# Control.net
KiCad netlist of a schematic drawn in Altium Designer
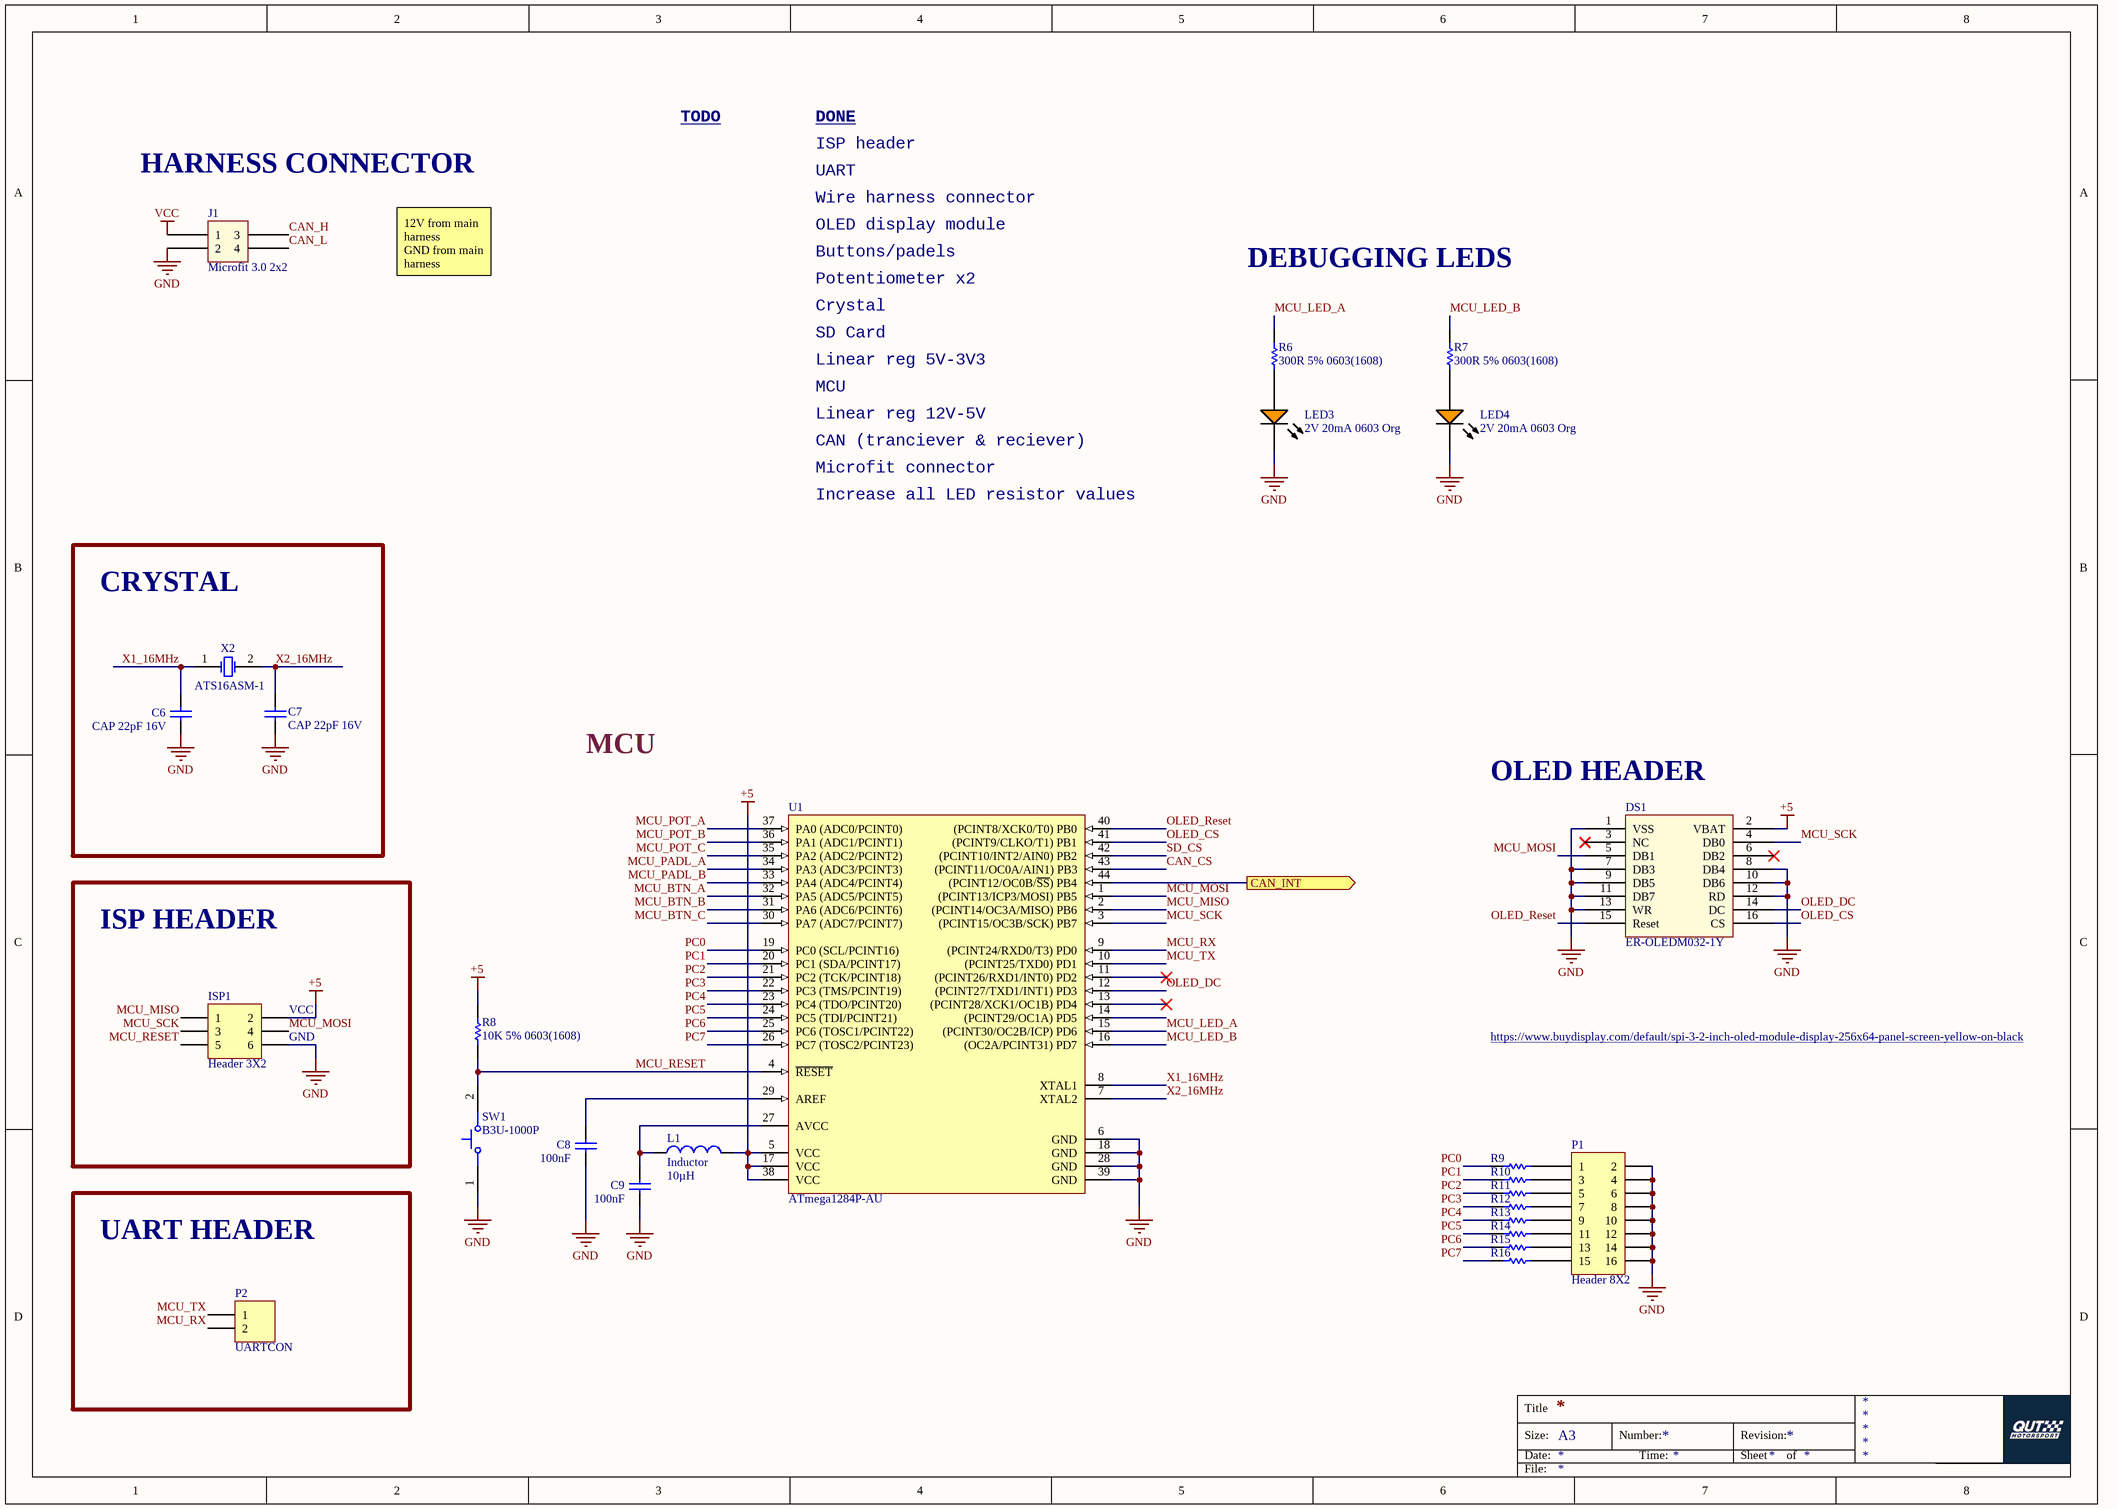
[diagram p0: Control.SchDoc]

(export (version "E")
  (design (tool "Eeschema 10.0.6"))
  (components
    (comp (ref "C6")
      (value "CAP 22pF 16V")
      (footprint "CAPC0603(1608)100_N")
      (description "CAP 22pF 16V ±5% 0603 (1608 Metric) Thickness 1mm SMD")
      (fields (field (name "TOLERANCE") "Â±5%"))
      (libsource (lib "Altium Content Vault") (part "CAP"))
    )
    (comp (ref "C7")
      (value "CAP 22pF 16V")
      (footprint "CAPC0603(1608)100_N")
      (description "CAP 22pF 16V ±5% 0603 (1608 Metric) Thickness 1mm SMD")
      (fields (field (name "TOLERANCE") "Â±5%"))
      (libsource (lib "Altium Content Vault") (part "CAP"))
    )
    (comp (ref "C8")
      (value "100nF")
      (footprint "CAPC0603(1608)100_M")
      (description "CAP 100nF 16V ±5% 0603 (1608 Metric) Thickness 1mm SMD")
      (fields (field (name "TOLERANCE") "Â±5%"))
      (libsource (lib "Altium Content Vault") (part "CAP"))
    )
    (comp (ref "C9")
      (value "100nF")
      (footprint "CAPC0603(1608)100_M")
      (description "CAP 100nF 16V ±5% 0603 (1608 Metric) Thickness 1mm SMD")
      (fields (field (name "TOLERANCE") "Â±5%"))
      (libsource (lib "Altium Content Vault") (part "CAP"))
    )
    (comp (ref "DS1")
      (value "ER-OLEDM032-1Y")
      (footprint "ER-OLEDM032-1Y")
      (description "SPI 3.2 inch OLED Module Display 256x64 Panel Screen,Yellow on Black")
      (libsource (lib "QUTMS_SteeringWheel") (part "ER-OLEDM032-1Y"))
    )
    (comp (ref "ISP1")
      (value "Header 3X2")
      (footprint "HDR2X3")
      (description "Header, 3-Pin, Dual row")
      (fields (field (name "PUBLISHER") "Altium Limited"))
      (libsource (lib "Miscellaneous Connectors") (part "Header 3X2"))
    )
    (comp (ref "J1")
      (value "Microfit 3.0 2x2")
      (footprint "Microfit_2X2_R_TH")
      (libsource (lib "QUTMS_Microfit") (part "Microfit_2x2"))
    )
    (comp (ref "L1")
      (value "Inductor")
      (footprint "0603")
      (fields (field (name "ALTIUM_VALUE") "10µH") (field (name "PUBLISHER") "Altium Limited"))
      (libsource (lib "Miscellaneous Devices") (part "Inductor"))
    )
    (comp (ref "LED3")
      (value "2V 20mA 0603 Org")
      (footprint "KING-LED0603-25-ORANGE_V")
      (description "LED, SMT, 0603(1608), 0.25mm Tthickness, Super Bright Orange")
      (fields (field (name "PARTNUMBER") "APG1608SEKC/T"))
      (libsource (lib "Altium Content Vault") (part "KING-LED_ORANGE_A1K2-2"))
    )
    (comp (ref "LED4")
      (value "2V 20mA 0603 Org")
      (footprint "KING-LED0603-25-ORANGE_V")
      (description "LED, SMT, 0603(1608), 0.25mm Tthickness, Super Bright Orange")
      (fields (field (name "PARTNUMBER") "APG1608SEKC/T"))
      (libsource (lib "Altium Content Vault") (part "KING-LED_ORANGE_A1K2-2"))
    )
    (comp (ref "P1")
      (value "Header 8X2")
      (footprint "HDR2X8")
      (description "Header, 8-Pin, Dual row")
      (fields (field (name "PUBLISHER") "Altium Limited"))
      (libsource (lib "Miscellaneous Connectors") (part "Header 8X2"))
    )
    (comp (ref "P2")
      (value "UARTCON")
      (footprint "HDR1X2")
      (description "Header, 2-Pin")
      (fields (field (name "PUBLISHER") "Altium Limited"))
      (libsource (lib "Miscellaneous Connectors") (part "Header 2"))
    )
    (comp (ref "R6")
      (value "300R 5% 0603(1608)")
      (footprint "RESC0603(1608)_N")
      (description "300R 0.1W 5% 0603 (1608 Metric)  SMD")
      (fields (field (name "TOLERANCE") "5 %") (field (name "POWER") "0.1 W"))
      (libsource (lib "Altium Content Vault") (part "RES"))
    )
    (comp (ref "R7")
      (value "300R 5% 0603(1608)")
      (footprint "RESC0603(1608)_N")
      (description "300R 0.1W 5% 0603 (1608 Metric)  SMD")
      (fields (field (name "TOLERANCE") "5 %") (field (name "POWER") "0.1 W"))
      (libsource (lib "Altium Content Vault") (part "RES"))
    )
    (comp (ref "R8")
      (value "10K 5% 0603(1608)")
      (footprint "RESC0603(1608)_N")
      (description "10K 0.1W 5% 0603 (1608 Metric)  SMD")
      (fields (field (name "TOLERANCE") "5 %") (field (name "POWER") "0.1 W"))
      (libsource (lib "Altium Content Vault") (part "RES"))
    )
    (comp (ref "R9")
      (value "JMP")
      (footprint "RESC0603(1608)_N")
      (description "300R 0.1W 5% 0603 (1608 Metric)  SMD")
      (fields (field (name "TOLERANCE") "5 %") (field (name "POWER") "0.1 W"))
      (libsource (lib "Altium Content Vault") (part "RES"))
    )
    (comp (ref "R10")
      (value "JMP")
      (footprint "RESC0603(1608)_N")
      (description "300R 0.1W 5% 0603 (1608 Metric)  SMD")
      (fields (field (name "TOLERANCE") "5 %") (field (name "POWER") "0.1 W"))
      (libsource (lib "Altium Content Vault") (part "RES"))
    )
    (comp (ref "R11")
      (value "JMP")
      (footprint "RESC0603(1608)_N")
      (description "300R 0.1W 5% 0603 (1608 Metric)  SMD")
      (fields (field (name "TOLERANCE") "5 %") (field (name "POWER") "0.1 W"))
      (libsource (lib "Altium Content Vault") (part "RES"))
    )
    (comp (ref "R12")
      (value "JMP")
      (footprint "RESC0603(1608)_N")
      (description "300R 0.1W 5% 0603 (1608 Metric)  SMD")
      (fields (field (name "TOLERANCE") "5 %") (field (name "POWER") "0.1 W"))
      (libsource (lib "Altium Content Vault") (part "RES"))
    )
    (comp (ref "R13")
      (value "JMP")
      (footprint "RESC0603(1608)_N")
      (description "300R 0.1W 5% 0603 (1608 Metric)  SMD")
      (fields (field (name "TOLERANCE") "5 %") (field (name "POWER") "0.1 W"))
      (libsource (lib "Altium Content Vault") (part "RES"))
    )
    (comp (ref "R14")
      (value "JMP")
      (footprint "RESC0603(1608)_N")
      (description "300R 0.1W 5% 0603 (1608 Metric)  SMD")
      (fields (field (name "TOLERANCE") "5 %") (field (name "POWER") "0.1 W"))
      (libsource (lib "Altium Content Vault") (part "RES"))
    )
    (comp (ref "R15")
      (value "JMP")
      (footprint "RESC0603(1608)_N")
      (description "300R 0.1W 5% 0603 (1608 Metric)  SMD")
      (fields (field (name "TOLERANCE") "5 %") (field (name "POWER") "0.1 W"))
      (libsource (lib "Altium Content Vault") (part "RES"))
    )
    (comp (ref "R16")
      (value "~")
      (footprint "RESC0603(1608)_N")
      (description "300R 0.1W 5% 0603 (1608 Metric)  SMD")
      (fields (field (name "TOLERANCE") "5 %") (field (name "POWER") "0.1 W"))
      (libsource (lib "Altium Content Vault") (part "RES"))
    )
    (comp (ref "SW1")
      (value "B3U-1000P")
      (footprint "OMRON-B3U-1000_V")
      (description "Ultra-Small Tactile Switch, 0.05 A, 12 V, -25 to 70 degC, 2-Pin SMD, RoHS, Tape and Reel")
      (fields (field (name "MANUFACTURER") "Omron Electronic Components"))
      (libsource (lib "Altium Content Vault") (part "SW-SPST-NO-2"))
    )
    (comp (ref "U1")
      (value "ATmega1284P-AU")
      (footprint "44A_N")
      (description "20 MHz 8-bit AVR Microcontroller with 128KB Flash, 44-Pin TQFP Pkg, Industrial Temp")
      (libsource (lib "Altium Content Vault") (part "MC-8B-ATmega1284P-44"))
    )
    (comp (ref "X2")
      (value "ATS16ASM-1")
      (footprint "CTS-ATS-SM-XTAL-2")
      (description "ATS-SM Series Quartz Crystal, 16 MHz, -20 to 70 degC, 11.1 x 4.83 x 4.3mm SMD, RoHS, Tape and Reel")
      (fields (field (name "MANUFACTURER") "CTS Corporation"))
      (libsource (lib "Altium Content Vault") (part "CTS-ATS-SM-XTAL-2"))
    )
  )
  (nets
    (net (code "1") (name "+5") (class "Default")
      (node (ref "DS1") (pin "2") (pinfunction "VBAT_2") (pintype "passive"))
      (node (ref "ISP1") (pin "2") (pinfunction "2_2") (pintype "passive"))
      (node (ref "L1") (pin "2") (pinfunction "2_2") (pintype "passive"))
      (node (ref "R8") (pin "2") (pinfunction "2_2") (pintype "passive"))
      (node (ref "U1") (pin "17") (pinfunction "VCC_17") (pintype "passive"))
      (node (ref "U1") (pin "38") (pinfunction "VCC_38") (pintype "passive"))
      (node (ref "U1") (pin "5") (pinfunction "VCC_5") (pintype "passive"))
    )
    (net (code "2") (name "/CAN_CS") (class "Default")
      (node (ref "U1") (pin "43") (pinfunction "(PCINT11/OC0A/AIN1)_PB3_43") (pintype "input"))
    )
    (net (code "3") (name "/CAN_H") (class "Default")
      (node (ref "J1") (pin "3") (pinfunction "3_3") (pintype "passive"))
    )
    (net (code "4") (name "/CAN_INT") (class "Default")
      (node (ref "U1") (pin "44") (pinfunction "(PCINT12/OC0B/~{SS})_PB4_44") (pintype "input"))
    )
    (net (code "5") (name "/CAN_L") (class "Default")
      (node (ref "J1") (pin "4") (pinfunction "4_4") (pintype "passive"))
    )
    (net (code "6") (name "/MCU_BTN_A") (class "Default")
      (node (ref "U1") (pin "32") (pinfunction "PA5_(ADC5/PCINT5)_32") (pintype "input"))
    )
    (net (code "7") (name "/MCU_BTN_B") (class "Default")
      (node (ref "U1") (pin "31") (pinfunction "PA6_(ADC6/PCINT6)_31") (pintype "input"))
    )
    (net (code "8") (name "/MCU_BTN_C") (class "Default")
      (node (ref "U1") (pin "30") (pinfunction "PA7_(ADC7/PCINT7)_30") (pintype "input"))
    )
    (net (code "9") (name "/MCU_LED_A") (class "Default")
      (node (ref "R6") (pin "2") (pinfunction "2_2") (pintype "passive"))
      (node (ref "U1") (pin "15") (pinfunction "(PCINT30/OC2B/ICP)_PD6_15") (pintype "input"))
    )
    (net (code "10") (name "/MCU_LED_B") (class "Default")
      (node (ref "R7") (pin "2") (pinfunction "2_2") (pintype "passive"))
      (node (ref "U1") (pin "16") (pinfunction "(OC2A/PCINT31)_PD7_16") (pintype "input"))
    )
    (net (code "11") (name "/MCU_MISO") (class "Default")
      (node (ref "ISP1") (pin "1") (pinfunction "1_1") (pintype "passive"))
      (node (ref "U1") (pin "2") (pinfunction "(PCINT14/OC3A/MISO)_PB6_2") (pintype "input"))
    )
    (net (code "12") (name "/MCU_MOSI") (class "Default")
      (node (ref "DS1") (pin "5") (pinfunction "DB1_5") (pintype "passive"))
      (node (ref "ISP1") (pin "4") (pinfunction "4_4") (pintype "passive"))
      (node (ref "U1") (pin "1") (pinfunction "(PCINT13/ICP3/MOSI)_PB5_1") (pintype "input"))
    )
    (net (code "13") (name "/MCU_PADL_A") (class "Default")
      (node (ref "U1") (pin "34") (pinfunction "PA3_(ADC3/PCINT3)_34") (pintype "input"))
    )
    (net (code "14") (name "/MCU_PADL_B") (class "Default")
      (node (ref "U1") (pin "33") (pinfunction "PA4_(ADC4/PCINT4)_33") (pintype "input"))
    )
    (net (code "15") (name "/MCU_POT_A") (class "Default")
      (node (ref "U1") (pin "37") (pinfunction "PA0_(ADC0/PCINT0)_37") (pintype "input"))
    )
    (net (code "16") (name "/MCU_POT_B") (class "Default")
      (node (ref "U1") (pin "36") (pinfunction "PA1_(ADC1/PCINT1)_36") (pintype "input"))
    )
    (net (code "17") (name "/MCU_POT_C") (class "Default")
      (node (ref "U1") (pin "35") (pinfunction "PA2_(ADC2/PCINT2)_35") (pintype "input"))
    )
    (net (code "18") (name "/MCU_RESET") (class "Default")
      (node (ref "ISP1") (pin "5") (pinfunction "5_5") (pintype "passive"))
      (node (ref "R8") (pin "1") (pinfunction "1_1") (pintype "passive"))
      (node (ref "SW1") (pin "2") (pinfunction "2_2") (pintype "passive"))
      (node (ref "U1") (pin "4") (pinfunction "~{RESET}_4") (pintype "input"))
    )
    (net (code "19") (name "/MCU_RX") (class "Default")
      (node (ref "P2") (pin "2") (pinfunction "2_2") (pintype "passive"))
      (node (ref "U1") (pin "9") (pinfunction "(PCINT24/RXD0/T3)_PD0_9") (pintype "input"))
    )
    (net (code "20") (name "/MCU_SCK") (class "Default")
      (node (ref "DS1") (pin "4") (pinfunction "DB0_4") (pintype "passive"))
      (node (ref "ISP1") (pin "3") (pinfunction "3_3") (pintype "passive"))
      (node (ref "U1") (pin "3") (pinfunction "(PCINT15/OC3B/SCK)_PB7_3") (pintype "input"))
    )
    (net (code "21") (name "/MCU_TX") (class "Default")
      (node (ref "P2") (pin "1") (pinfunction "1_1") (pintype "passive"))
      (node (ref "U1") (pin "10") (pinfunction "(PCINT25/TXD0)_PD1_10") (pintype "input"))
    )
    (net (code "22") (name "/OLED_CS") (class "Default")
      (node (ref "DS1") (pin "16") (pinfunction "CS_16") (pintype "passive"))
      (node (ref "U1") (pin "41") (pinfunction "(PCINT9/CLKO/T1)_PB1_41") (pintype "input"))
    )
    (net (code "23") (name "/OLED_DC") (class "Default")
      (node (ref "DS1") (pin "14") (pinfunction "DC_14") (pintype "passive"))
      (node (ref "U1") (pin "12") (pinfunction "(PCINT27/TXD1/INT1)_PD3_12") (pintype "input"))
    )
    (net (code "24") (name "/OLED_Reset") (class "Default")
      (node (ref "DS1") (pin "15") (pinfunction "Reset_15") (pintype "passive"))
      (node (ref "U1") (pin "40") (pinfunction "(PCINT8/XCK0/T0)_PB0_40") (pintype "input"))
    )
    (net (code "25") (name "/PC0") (class "Default")
      (node (ref "R9") (pin "2") (pinfunction "2_2") (pintype "passive"))
      (node (ref "U1") (pin "19") (pinfunction "PC0_(SCL/PCINT16)_19") (pintype "input"))
    )
    (net (code "26") (name "/PC1") (class "Default")
      (node (ref "R10") (pin "2") (pinfunction "2_2") (pintype "passive"))
      (node (ref "U1") (pin "20") (pinfunction "PC1_(SDA/PCINT17)_20") (pintype "input"))
    )
    (net (code "27") (name "/PC2") (class "Default")
      (node (ref "R11") (pin "2") (pinfunction "2_2") (pintype "passive"))
      (node (ref "U1") (pin "21") (pinfunction "PC2_(TCK/PCINT18)_21") (pintype "input"))
    )
    (net (code "28") (name "/PC3") (class "Default")
      (node (ref "R12") (pin "2") (pinfunction "2_2") (pintype "passive"))
      (node (ref "U1") (pin "22") (pinfunction "PC3_(TMS/PCINT19)_22") (pintype "input"))
    )
    (net (code "29") (name "/PC4") (class "Default")
      (node (ref "R13") (pin "2") (pinfunction "2_2") (pintype "passive"))
      (node (ref "U1") (pin "23") (pinfunction "PC4_(TDO/PCINT20)_23") (pintype "input"))
    )
    (net (code "30") (name "/PC5") (class "Default")
      (node (ref "R14") (pin "2") (pinfunction "2_2") (pintype "passive"))
      (node (ref "U1") (pin "24") (pinfunction "PC5_(TDI/PCINT21)_24") (pintype "input"))
    )
    (net (code "31") (name "/PC6") (class "Default")
      (node (ref "R15") (pin "2") (pinfunction "2_2") (pintype "passive"))
      (node (ref "U1") (pin "25") (pinfunction "PC6_(TOSC1/PCINT22)_25") (pintype "input"))
    )
    (net (code "32") (name "/PC7") (class "Default")
      (node (ref "R16") (pin "2") (pinfunction "2_2") (pintype "passive"))
      (node (ref "U1") (pin "26") (pinfunction "PC7_(TOSC2/PCINT23)_26") (pintype "input"))
    )
    (net (code "33") (name "/SD_CS") (class "Default")
      (node (ref "U1") (pin "42") (pinfunction "(PCINT10/INT2/AIN0)_PB2_42") (pintype "input"))
    )
    (net (code "34") (name "/X1_16MHz") (class "Default")
      (node (ref "C6") (pin "2") (pinfunction "2_2") (pintype "passive"))
      (node (ref "U1") (pin "8") (pinfunction "XTAL1_8") (pintype "passive"))
      (node (ref "X2") (pin "1") (pinfunction "X1_1") (pintype "passive"))
    )
    (net (code "35") (name "/X2_16MHz") (class "Default")
      (node (ref "C7") (pin "1") (pinfunction "1_1") (pintype "passive"))
      (node (ref "U1") (pin "7") (pinfunction "XTAL2_7") (pintype "passive"))
      (node (ref "X2") (pin "2") (pinfunction "X2_2") (pintype "passive"))
    )
    (net (code "36") (name "GND") (class "Default")
      (node (ref "C6") (pin "1") (pinfunction "1_1") (pintype "passive"))
      (node (ref "C7") (pin "2") (pinfunction "2_2") (pintype "passive"))
      (node (ref "C8") (pin "1") (pinfunction "1_1") (pintype "passive"))
      (node (ref "C9") (pin "1") (pinfunction "1_1") (pintype "passive"))
      (node (ref "DS1") (pin "1") (pinfunction "VSS_1") (pintype "passive"))
      (node (ref "DS1") (pin "10") (pinfunction "DB6_10") (pintype "passive"))
      (node (ref "DS1") (pin "11") (pinfunction "DB7_11") (pintype "passive"))
      (node (ref "DS1") (pin "12") (pinfunction "RD_12") (pintype "passive"))
      (node (ref "DS1") (pin "13") (pinfunction "WR_13") (pintype "passive"))
      (node (ref "DS1") (pin "7") (pinfunction "DB3_7") (pintype "passive"))
      (node (ref "DS1") (pin "8") (pinfunction "DB4_8") (pintype "passive"))
      (node (ref "DS1") (pin "9") (pinfunction "DB5_9") (pintype "passive"))
      (node (ref "ISP1") (pin "6") (pinfunction "6_6") (pintype "passive"))
      (node (ref "J1") (pin "2") (pinfunction "2_2") (pintype "passive"))
      (node (ref "LED3") (pin "2") (pinfunction "K_2") (pintype "passive"))
      (node (ref "LED4") (pin "2") (pinfunction "K_2") (pintype "passive"))
      (node (ref "P1") (pin "10") (pinfunction "10_10") (pintype "passive"))
      (node (ref "P1") (pin "12") (pinfunction "12_12") (pintype "passive"))
      (node (ref "P1") (pin "14") (pinfunction "14_14") (pintype "passive"))
      (node (ref "P1") (pin "16") (pinfunction "16_16") (pintype "passive"))
      (node (ref "P1") (pin "2") (pinfunction "2_2") (pintype "passive"))
      (node (ref "P1") (pin "4") (pinfunction "4_4") (pintype "passive"))
      (node (ref "P1") (pin "6") (pinfunction "6_6") (pintype "passive"))
      (node (ref "P1") (pin "8") (pinfunction "8_8") (pintype "passive"))
      (node (ref "SW1") (pin "1") (pinfunction "1_1") (pintype "passive"))
      (node (ref "U1") (pin "18") (pinfunction "GND_18") (pintype "passive"))
      (node (ref "U1") (pin "28") (pinfunction "GND_28") (pintype "passive"))
      (node (ref "U1") (pin "39") (pinfunction "GND_39") (pintype "passive"))
      (node (ref "U1") (pin "6") (pinfunction "GND_6") (pintype "passive"))
    )
    (net (code "37") (name "Net-(LED3-A)") (class "Default")
      (node (ref "LED3") (pin "1") (pinfunction "A_1") (pintype "passive"))
      (node (ref "R6") (pin "1") (pinfunction "1_1") (pintype "passive"))
    )
    (net (code "38") (name "Net-(LED4-A)") (class "Default")
      (node (ref "LED4") (pin "1") (pinfunction "A_1") (pintype "passive"))
      (node (ref "R7") (pin "1") (pinfunction "1_1") (pintype "passive"))
    )
    (net (code "39") (name "Net-(P1-Pad1)") (class "Default")
      (node (ref "P1") (pin "1") (pinfunction "1_1") (pintype "passive"))
      (node (ref "R9") (pin "1") (pinfunction "1_1") (pintype "passive"))
    )
    (net (code "40") (name "Net-(P1-Pad3)") (class "Default")
      (node (ref "P1") (pin "3") (pinfunction "3_3") (pintype "passive"))
      (node (ref "R10") (pin "1") (pinfunction "1_1") (pintype "passive"))
    )
    (net (code "41") (name "Net-(P1-Pad5)") (class "Default")
      (node (ref "P1") (pin "5") (pinfunction "5_5") (pintype "passive"))
      (node (ref "R11") (pin "1") (pinfunction "1_1") (pintype "passive"))
    )
    (net (code "42") (name "Net-(P1-Pad7)") (class "Default")
      (node (ref "P1") (pin "7") (pinfunction "7_7") (pintype "passive"))
      (node (ref "R12") (pin "1") (pinfunction "1_1") (pintype "passive"))
    )
    (net (code "43") (name "Net-(P1-Pad9)") (class "Default")
      (node (ref "P1") (pin "9") (pinfunction "9_9") (pintype "passive"))
      (node (ref "R13") (pin "1") (pinfunction "1_1") (pintype "passive"))
    )
    (net (code "44") (name "Net-(P1-Pad11)") (class "Default")
      (node (ref "P1") (pin "11") (pinfunction "11_11") (pintype "passive"))
      (node (ref "R14") (pin "1") (pinfunction "1_1") (pintype "passive"))
    )
    (net (code "45") (name "Net-(P1-Pad13)") (class "Default")
      (node (ref "P1") (pin "13") (pinfunction "13_13") (pintype "passive"))
      (node (ref "R15") (pin "1") (pinfunction "1_1") (pintype "passive"))
    )
    (net (code "46") (name "Net-(P1-Pad15)") (class "Default")
      (node (ref "P1") (pin "15") (pinfunction "15_15") (pintype "passive"))
      (node (ref "R16") (pin "1") (pinfunction "1_1") (pintype "passive"))
    )
    (net (code "47") (name "Net-(U1-AREF)") (class "Default")
      (node (ref "C8") (pin "2") (pinfunction "2_2") (pintype "passive"))
      (node (ref "U1") (pin "29") (pinfunction "AREF_29") (pintype "input"))
    )
    (net (code "48") (name "Net-(U1-AVCC)") (class "Default")
      (node (ref "C9") (pin "2") (pinfunction "2_2") (pintype "passive"))
      (node (ref "L1") (pin "1") (pinfunction "1_1") (pintype "passive"))
      (node (ref "U1") (pin "27") (pinfunction "AVCC_27") (pintype "passive"))
    )
    (net (code "49") (name "VCC") (class "Default")
      (node (ref "J1") (pin "1") (pinfunction "1_1") (pintype "passive"))
    )
    (net (code "50") (name "unconnected-(DS1-DB2-Pad6)") (class "Default")
      (node (ref "DS1") (pin "6") (pinfunction "DB2_6") (pintype "passive+no_connect"))
    )
    (net (code "51") (name "unconnected-(DS1-NC-Pad3)") (class "Default")
      (node (ref "DS1") (pin "3") (pinfunction "NC_3") (pintype "passive+no_connect"))
    )
    (net (code "52") (name "unconnected-(U1-(PCINT26{slash}RXD1{slash}INT0)_PD2-Pad11)") (class "Default")
      (node (ref "U1") (pin "11") (pinfunction "(PCINT26/RXD1/INT0)_PD2_11") (pintype "input+no_connect"))
    )
    (net (code "53") (name "unconnected-(U1-(PCINT28{slash}XCK1{slash}OC1B)_PD4-Pad13)") (class "Default")
      (node (ref "U1") (pin "13") (pinfunction "(PCINT28/XCK1/OC1B)_PD4_13") (pintype "input+no_connect"))
    )
    (net (code "54") (name "unconnected-(U1-(PCINT29{slash}OC1A)_PD5-Pad14)") (class "Default")
      (node (ref "U1") (pin "14") (pinfunction "(PCINT29/OC1A)_PD5_14") (pintype "input"))
    )
  )
)
